# press-control.net
KiCad netlist of a schematic drawn in EAGLE
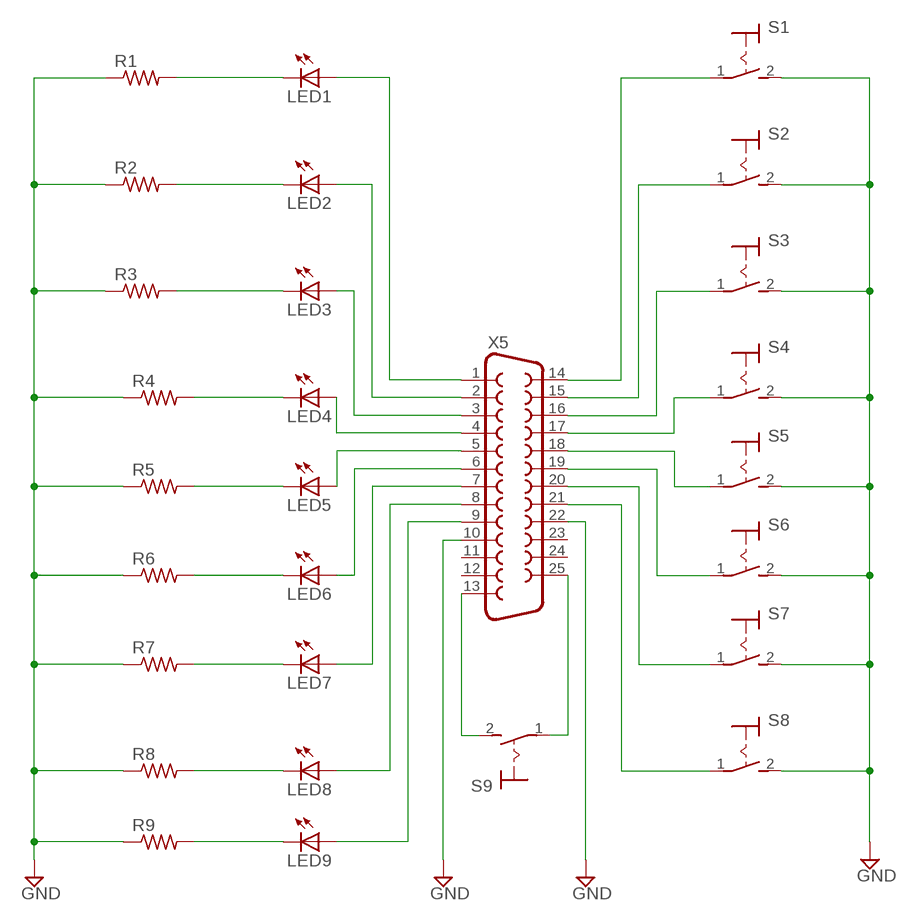
[diagram p0: schematic, sheet 1]

(export (version "E")
  (design (tool "Eeschema 10.0.6"))
  (components
    (comp (ref "LED1")
      (value "LED5MM")
      (footprint "eagle-import:LED5MM")
      (libsource (lib "eagle-import") (part "LED5MM"))
    )
    (comp (ref "LED2")
      (value "LED5MM")
      (footprint "eagle-import:LED5MM")
      (libsource (lib "eagle-import") (part "LED5MM"))
    )
    (comp (ref "LED3")
      (value "LED5MM")
      (footprint "eagle-import:LED5MM")
      (libsource (lib "eagle-import") (part "LED5MM"))
    )
    (comp (ref "LED4")
      (value "LED5MM")
      (footprint "eagle-import:LED5MM")
      (libsource (lib "eagle-import") (part "LED5MM"))
    )
    (comp (ref "LED5")
      (value "LED5MM")
      (footprint "eagle-import:LED5MM")
      (libsource (lib "eagle-import") (part "LED5MM"))
    )
    (comp (ref "LED6")
      (value "LED5MM")
      (footprint "eagle-import:LED5MM")
      (libsource (lib "eagle-import") (part "LED5MM"))
    )
    (comp (ref "LED7")
      (value "LED5MM")
      (footprint "eagle-import:LED5MM")
      (libsource (lib "eagle-import") (part "LED5MM"))
    )
    (comp (ref "LED8")
      (value "LED5MM")
      (footprint "eagle-import:LED5MM")
      (libsource (lib "eagle-import") (part "LED5MM"))
    )
    (comp (ref "LED9")
      (value "LED5MM")
      (footprint "eagle-import:LED5MM")
      (libsource (lib "eagle-import") (part "LED5MM"))
    )
    (comp (ref "R1")
      (value "R-US_0207/10")
      (footprint "eagle-import:0207_10")
      (libsource (lib "eagle-import") (part "R-US_0207/10"))
    )
    (comp (ref "R2")
      (value "R-US_0207/10")
      (footprint "eagle-import:0207_10")
      (libsource (lib "eagle-import") (part "R-US_0207/10"))
    )
    (comp (ref "R3")
      (value "R-US_0207/10")
      (footprint "eagle-import:0207_10")
      (libsource (lib "eagle-import") (part "R-US_0207/10"))
    )
    (comp (ref "R4")
      (value "R-US_0207/10")
      (footprint "eagle-import:0207_10")
      (libsource (lib "eagle-import") (part "R-US_0207/10"))
    )
    (comp (ref "R5")
      (value "R-US_0207/10")
      (footprint "eagle-import:0207_10")
      (libsource (lib "eagle-import") (part "R-US_0207/10"))
    )
    (comp (ref "R6")
      (value "R-US_0207/10")
      (footprint "eagle-import:0207_10")
      (libsource (lib "eagle-import") (part "R-US_0207/10"))
    )
    (comp (ref "R7")
      (value "R-US_0207/10")
      (footprint "eagle-import:0207_10")
      (libsource (lib "eagle-import") (part "R-US_0207/10"))
    )
    (comp (ref "R8")
      (value "R-US_0207/10")
      (footprint "eagle-import:0207_10")
      (libsource (lib "eagle-import") (part "R-US_0207/10"))
    )
    (comp (ref "R9")
      (value "R-US_0207/10")
      (footprint "eagle-import:0207_10")
      (libsource (lib "eagle-import") (part "R-US_0207/10"))
    )
    (comp (ref "S1")
      (value "MS243")
      (footprint "eagle-import:MS243")
      (libsource (lib "eagle-import") (part "MS243"))
    )
    (comp (ref "S2")
      (value "MS243")
      (footprint "eagle-import:MS243")
      (libsource (lib "eagle-import") (part "MS243"))
    )
    (comp (ref "S3")
      (value "MS243")
      (footprint "eagle-import:MS243")
      (libsource (lib "eagle-import") (part "MS243"))
    )
    (comp (ref "S4")
      (value "MS243")
      (footprint "eagle-import:MS243")
      (libsource (lib "eagle-import") (part "MS243"))
    )
    (comp (ref "S5")
      (value "MS243")
      (footprint "eagle-import:MS243")
      (libsource (lib "eagle-import") (part "MS243"))
    )
    (comp (ref "S6")
      (value "MS243")
      (footprint "eagle-import:MS243")
      (libsource (lib "eagle-import") (part "MS243"))
    )
    (comp (ref "S7")
      (value "MS243")
      (footprint "eagle-import:MS243")
      (libsource (lib "eagle-import") (part "MS243"))
    )
    (comp (ref "S8")
      (value "MS243")
      (footprint "eagle-import:MS243")
      (libsource (lib "eagle-import") (part "MS243"))
    )
    (comp (ref "S9")
      (value "MS243")
      (footprint "eagle-import:MS243")
      (libsource (lib "eagle-import") (part "MS243"))
    )
    (comp (ref "X5")
      (value "DB25_FEMALEV")
      (footprint "eagle-import:F25V")
      (libsource (lib "eagle-import") (part "DB25_FEMALEV"))
    )
  )
  (nets
    (net (code "1") (name "GND") (class "Default")
      (node (ref "R1") (pin "1") (pinfunction "1_1") (pintype "passive"))
      (node (ref "R2") (pin "1") (pinfunction "1_1") (pintype "passive"))
      (node (ref "R3") (pin "1") (pinfunction "1_1") (pintype "passive"))
      (node (ref "R4") (pin "1") (pinfunction "1_1") (pintype "passive"))
      (node (ref "R5") (pin "1") (pinfunction "1_1") (pintype "passive"))
      (node (ref "R6") (pin "1") (pinfunction "1_1") (pintype "passive"))
      (node (ref "R7") (pin "1") (pinfunction "1_1") (pintype "passive"))
      (node (ref "R8") (pin "1") (pinfunction "1_1") (pintype "passive"))
      (node (ref "R9") (pin "1") (pinfunction "1_1") (pintype "passive"))
      (node (ref "S1") (pin "2") (pinfunction "S_2") (pintype "passive"))
      (node (ref "S2") (pin "2") (pinfunction "S_2") (pintype "passive"))
      (node (ref "S3") (pin "2") (pinfunction "S_2") (pintype "passive"))
      (node (ref "S4") (pin "2") (pinfunction "S_2") (pintype "passive"))
      (node (ref "S5") (pin "2") (pinfunction "S_2") (pintype "passive"))
      (node (ref "S6") (pin "2") (pinfunction "S_2") (pintype "passive"))
      (node (ref "S7") (pin "2") (pinfunction "S_2") (pintype "passive"))
      (node (ref "S8") (pin "2") (pinfunction "S_2") (pintype "passive"))
      (node (ref "X5") (pin "10") (pinfunction "10_10") (pintype "passive"))
      (node (ref "X5") (pin "22") (pinfunction "22_22") (pintype "passive"))
    )
    (net (code "2") (name "Net-(LED1-C)") (class "Default")
      (node (ref "LED1") (pin "K") (pinfunction "C_K") (pintype "passive"))
      (node (ref "R1") (pin "2") (pinfunction "2_2") (pintype "passive"))
    )
    (net (code "3") (name "Net-(LED1-PadA)") (class "Default")
      (node (ref "LED1") (pin "A") (pinfunction "A_A") (pintype "passive"))
      (node (ref "X5") (pin "1") (pinfunction "1_1") (pintype "passive"))
    )
    (net (code "4") (name "Net-(LED2-C)") (class "Default")
      (node (ref "LED2") (pin "K") (pinfunction "C_K") (pintype "passive"))
      (node (ref "R2") (pin "2") (pinfunction "2_2") (pintype "passive"))
    )
    (net (code "5") (name "Net-(LED2-PadA)") (class "Default")
      (node (ref "LED2") (pin "A") (pinfunction "A_A") (pintype "passive"))
      (node (ref "X5") (pin "2") (pinfunction "2_2") (pintype "passive"))
    )
    (net (code "6") (name "Net-(LED3-C)") (class "Default")
      (node (ref "LED3") (pin "K") (pinfunction "C_K") (pintype "passive"))
      (node (ref "R3") (pin "2") (pinfunction "2_2") (pintype "passive"))
    )
    (net (code "7") (name "Net-(LED3-PadA)") (class "Default")
      (node (ref "LED3") (pin "A") (pinfunction "A_A") (pintype "passive"))
      (node (ref "X5") (pin "3") (pinfunction "3_3") (pintype "passive"))
    )
    (net (code "8") (name "Net-(LED4-C)") (class "Default")
      (node (ref "LED4") (pin "K") (pinfunction "C_K") (pintype "passive"))
      (node (ref "R4") (pin "2") (pinfunction "2_2") (pintype "passive"))
    )
    (net (code "9") (name "Net-(LED4-PadA)") (class "Default")
      (node (ref "LED4") (pin "A") (pinfunction "A_A") (pintype "passive"))
      (node (ref "X5") (pin "4") (pinfunction "4_4") (pintype "passive"))
    )
    (net (code "10") (name "Net-(LED5-C)") (class "Default")
      (node (ref "LED5") (pin "K") (pinfunction "C_K") (pintype "passive"))
      (node (ref "R5") (pin "2") (pinfunction "2_2") (pintype "passive"))
    )
    (net (code "11") (name "Net-(LED5-PadA)") (class "Default")
      (node (ref "LED5") (pin "A") (pinfunction "A_A") (pintype "passive"))
      (node (ref "X5") (pin "5") (pinfunction "5_5") (pintype "passive"))
    )
    (net (code "12") (name "Net-(LED6-C)") (class "Default")
      (node (ref "LED6") (pin "K") (pinfunction "C_K") (pintype "passive"))
      (node (ref "R6") (pin "2") (pinfunction "2_2") (pintype "passive"))
    )
    (net (code "13") (name "Net-(LED6-PadA)") (class "Default")
      (node (ref "LED6") (pin "A") (pinfunction "A_A") (pintype "passive"))
      (node (ref "X5") (pin "6") (pinfunction "6_6") (pintype "passive"))
    )
    (net (code "14") (name "Net-(LED7-C)") (class "Default")
      (node (ref "LED7") (pin "K") (pinfunction "C_K") (pintype "passive"))
      (node (ref "R7") (pin "2") (pinfunction "2_2") (pintype "passive"))
    )
    (net (code "15") (name "Net-(LED7-PadA)") (class "Default")
      (node (ref "LED7") (pin "A") (pinfunction "A_A") (pintype "passive"))
      (node (ref "X5") (pin "7") (pinfunction "7_7") (pintype "passive"))
    )
    (net (code "16") (name "Net-(LED8-C)") (class "Default")
      (node (ref "LED8") (pin "K") (pinfunction "C_K") (pintype "passive"))
      (node (ref "R8") (pin "2") (pinfunction "2_2") (pintype "passive"))
    )
    (net (code "17") (name "Net-(LED8-PadA)") (class "Default")
      (node (ref "LED8") (pin "A") (pinfunction "A_A") (pintype "passive"))
      (node (ref "X5") (pin "8") (pinfunction "8_8") (pintype "passive"))
    )
    (net (code "18") (name "Net-(LED9-C)") (class "Default")
      (node (ref "LED9") (pin "K") (pinfunction "C_K") (pintype "passive"))
      (node (ref "R9") (pin "2") (pinfunction "2_2") (pintype "passive"))
    )
    (net (code "19") (name "Net-(LED9-PadA)") (class "Default")
      (node (ref "LED9") (pin "A") (pinfunction "A_A") (pintype "passive"))
      (node (ref "X5") (pin "9") (pinfunction "9_9") (pintype "passive"))
    )
    (net (code "20") (name "Net-(S1-P)") (class "Default")
      (node (ref "S1") (pin "1") (pinfunction "P_1") (pintype "passive"))
      (node (ref "X5") (pin "14") (pinfunction "14_14") (pintype "passive"))
    )
    (net (code "21") (name "Net-(S2-P)") (class "Default")
      (node (ref "S2") (pin "1") (pinfunction "P_1") (pintype "passive"))
      (node (ref "X5") (pin "15") (pinfunction "15_15") (pintype "passive"))
    )
    (net (code "22") (name "Net-(S3-P)") (class "Default")
      (node (ref "S3") (pin "1") (pinfunction "P_1") (pintype "passive"))
      (node (ref "X5") (pin "16") (pinfunction "16_16") (pintype "passive"))
    )
    (net (code "23") (name "Net-(S4-P)") (class "Default")
      (node (ref "S4") (pin "1") (pinfunction "P_1") (pintype "passive"))
      (node (ref "X5") (pin "17") (pinfunction "17_17") (pintype "passive"))
    )
    (net (code "24") (name "Net-(S5-P)") (class "Default")
      (node (ref "S5") (pin "1") (pinfunction "P_1") (pintype "passive"))
      (node (ref "X5") (pin "18") (pinfunction "18_18") (pintype "passive"))
    )
    (net (code "25") (name "Net-(S6-P)") (class "Default")
      (node (ref "S6") (pin "1") (pinfunction "P_1") (pintype "passive"))
      (node (ref "X5") (pin "19") (pinfunction "19_19") (pintype "passive"))
    )
    (net (code "26") (name "Net-(S7-P)") (class "Default")
      (node (ref "S7") (pin "1") (pinfunction "P_1") (pintype "passive"))
      (node (ref "X5") (pin "20") (pinfunction "20_20") (pintype "passive"))
    )
    (net (code "27") (name "Net-(S8-P)") (class "Default")
      (node (ref "S8") (pin "1") (pinfunction "P_1") (pintype "passive"))
      (node (ref "X5") (pin "21") (pinfunction "21_21") (pintype "passive"))
    )
    (net (code "28") (name "Net-(S9-P)") (class "Default")
      (node (ref "S9") (pin "1") (pinfunction "P_1") (pintype "passive"))
      (node (ref "X5") (pin "25") (pinfunction "25_25") (pintype "passive"))
    )
    (net (code "29") (name "Net-(S9-S)") (class "Default")
      (node (ref "S9") (pin "2") (pinfunction "S_2") (pintype "passive"))
      (node (ref "X5") (pin "13") (pinfunction "13_13") (pintype "passive"))
    )
    (net (code "30") (name "unconnected-(X5-Pad11)") (class "Default")
      (node (ref "X5") (pin "11") (pinfunction "11_11") (pintype "passive"))
    )
    (net (code "31") (name "unconnected-(X5-Pad12)") (class "Default")
      (node (ref "X5") (pin "12") (pinfunction "12_12") (pintype "passive"))
    )
    (net (code "32") (name "unconnected-(X5-Pad23)") (class "Default")
      (node (ref "X5") (pin "23") (pinfunction "23_23") (pintype "passive"))
    )
    (net (code "33") (name "unconnected-(X5-Pad24)") (class "Default")
      (node (ref "X5") (pin "24") (pinfunction "24_24") (pintype "passive"))
    )
  )
)
